# Motor_Schem_1.net
KiCad netlist of a schematic drawn in Altium Designer
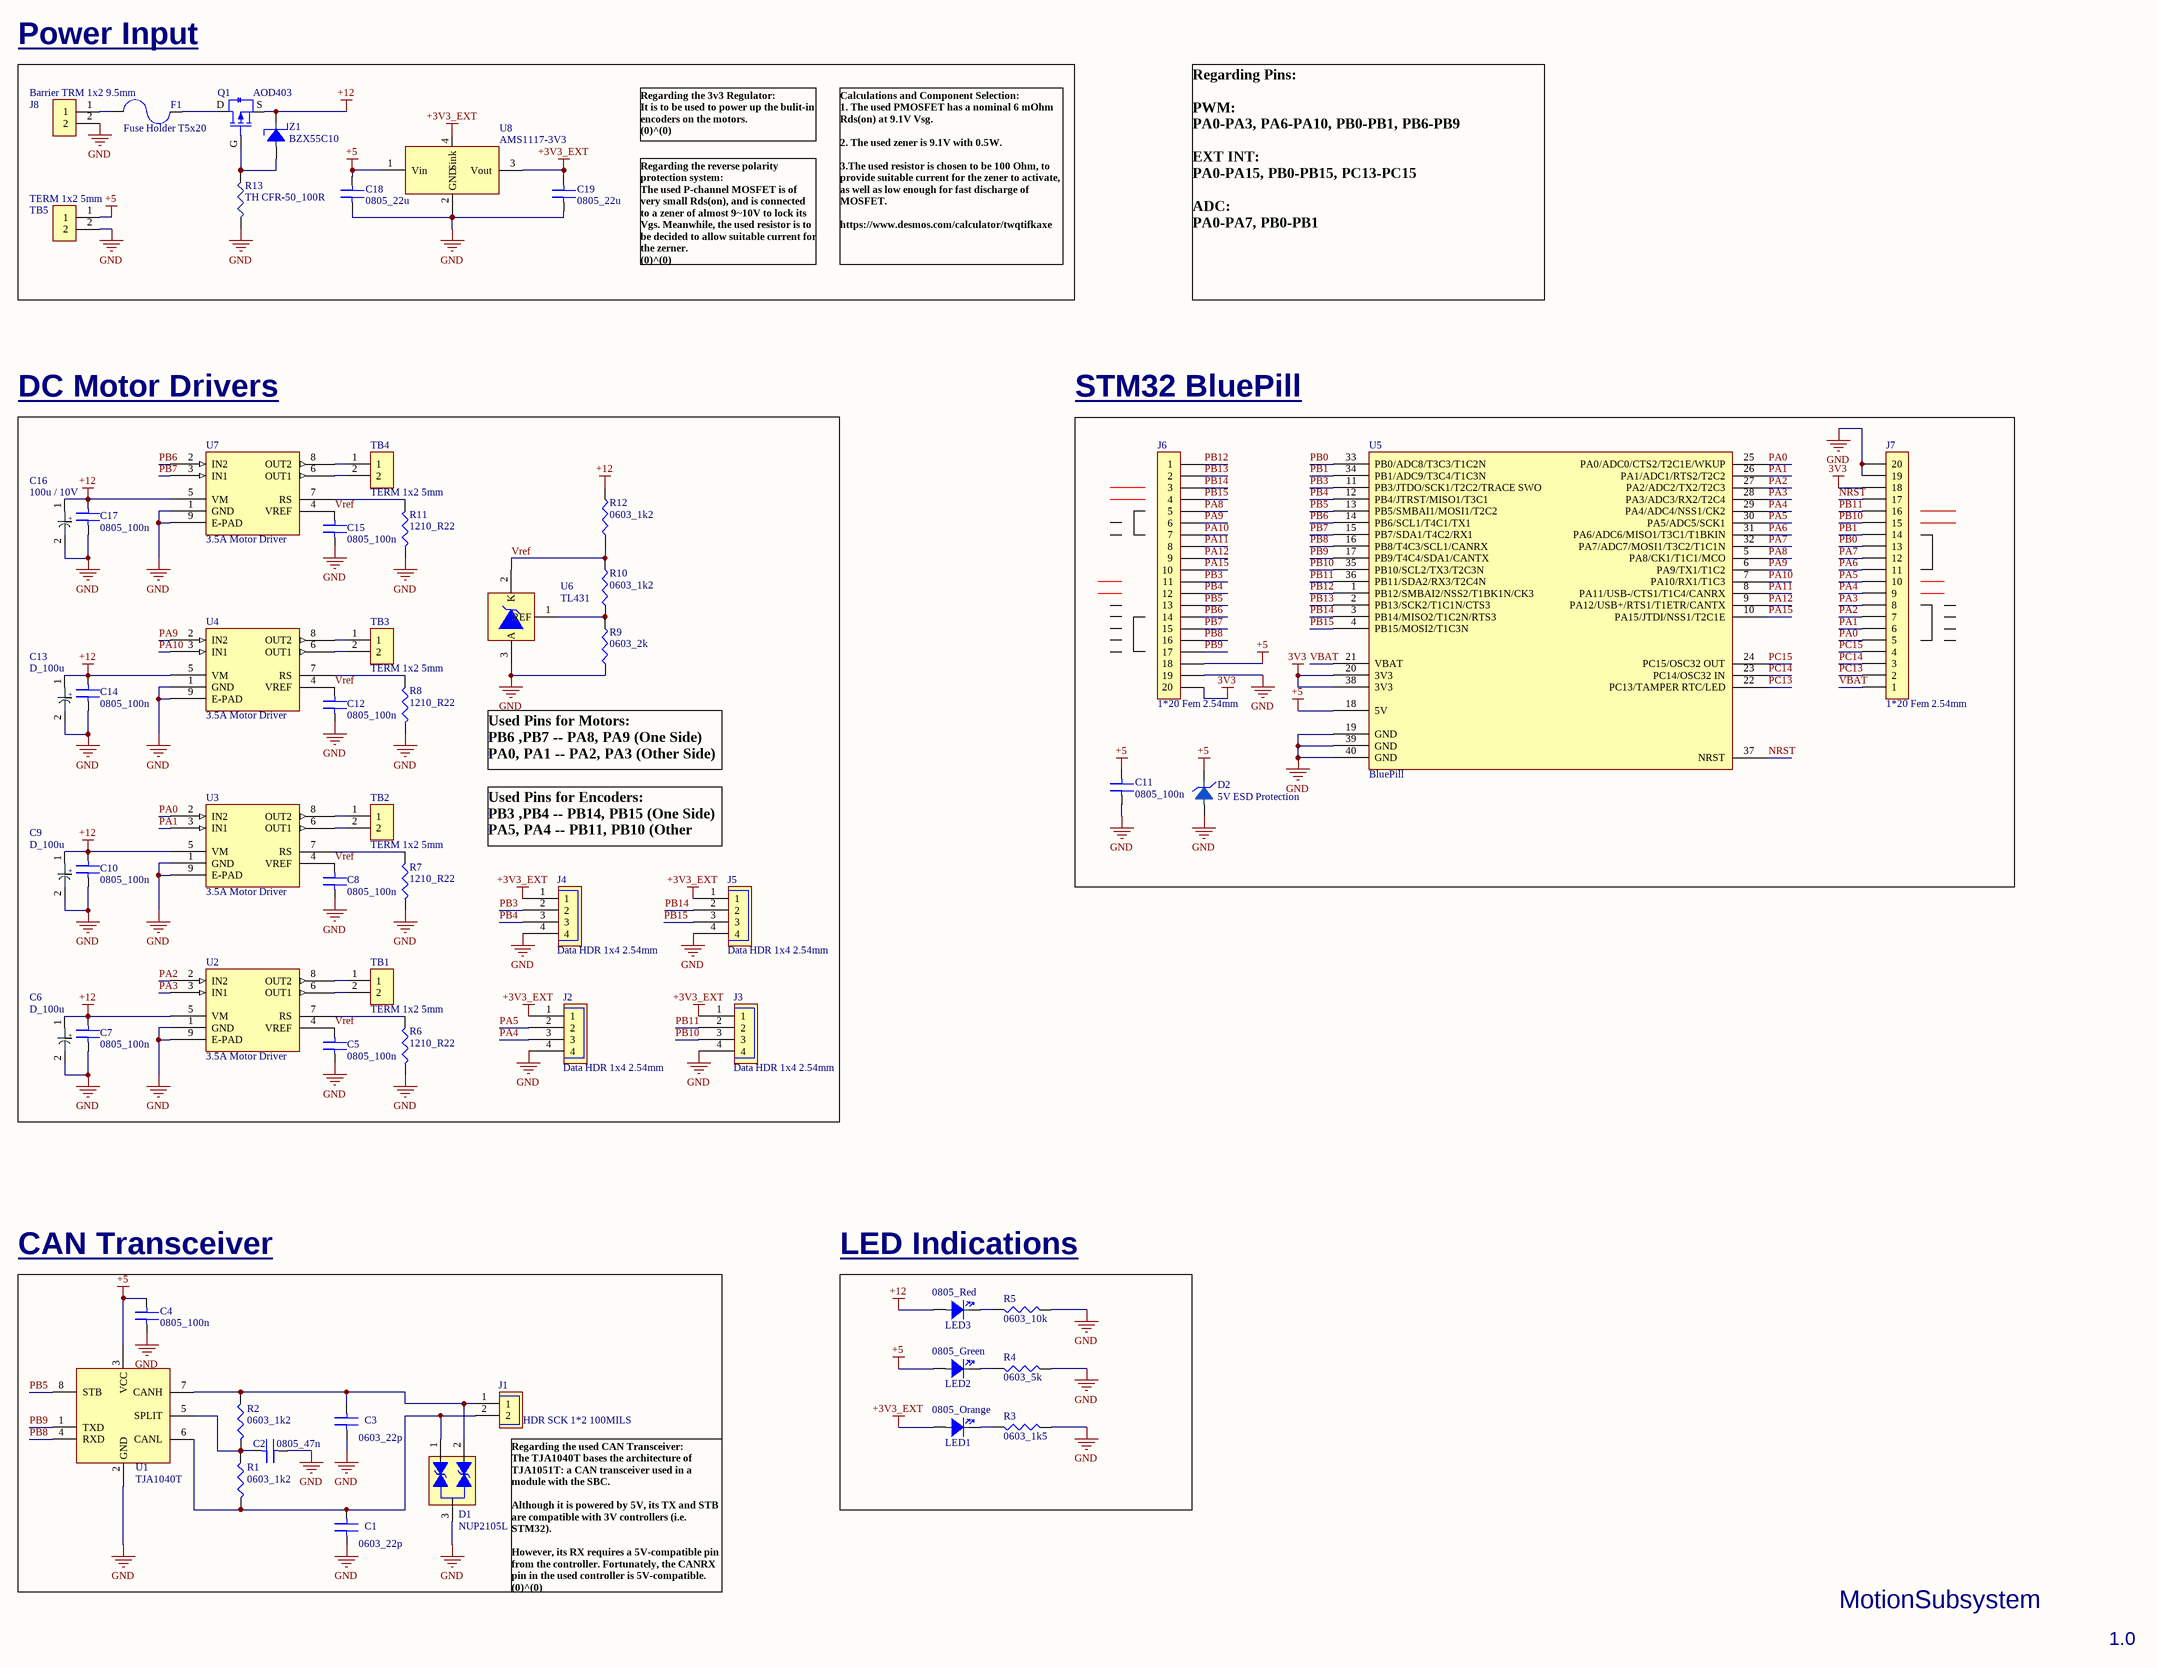
[diagram p0: Motor_Schem_1.SchDoc]

(export (version "E")
  (design (tool "Eeschema 10.0.6"))
  (components
    (comp (ref "C1")
      (value "0603_22p")
      (footprint "0603_CAP")
      (libsource (lib "TimerSMD_Components") (part "0603 Capacitor"))
    )
    (comp (ref "C2")
      (value "0805_47n")
      (footprint "C0805 - 0.1uf")
      (fields (field (name "TOLERANCE") "10%") (field (name "VOLTAGE") "25V"))
      (libsource (lib "TimerSMD_Components") (part "C2012X5R1E105K125AA"))
    )
    (comp (ref "C3")
      (value "0603_22p")
      (footprint "0603_CAP")
      (libsource (lib "TimerSMD_Components") (part "0603 Capacitor"))
    )
    (comp (ref "C4")
      (value "0805_100n")
      (footprint "C0805 - 0.1uf")
      (fields (field (name "TOLERANCE") "10%") (field (name "VOLTAGE") "25V"))
      (libsource (lib "TimerSMD_Components") (part "C2012X5R1E105K125AA"))
    )
    (comp (ref "C5")
      (value "0805_100n")
      (footprint "C0805 - 0.1uf")
      (fields (field (name "TOLERANCE") "10%") (field (name "VOLTAGE") "25V"))
      (libsource (lib "TimerSMD_Components") (part "C2012X5R1E105K125AA"))
    )
    (comp (ref "C6")
      (value "D_100u")
      (footprint "C_ALUM_D_SIZE")
      (description "Cap Aluminum 100uF 10V 20% (5 X 5.4mm) SMD 50mA 1000 hr 85°C T/R")
      (fields (field (name "TOLERANCE") "20%"))
      (libsource (lib "TimerSMD_Components") (part "EEE-1AA101WR"))
    )
    (comp (ref "C7")
      (value "0805_100n")
      (footprint "C0805 - 0.1uf")
      (fields (field (name "TOLERANCE") "10%") (field (name "VOLTAGE") "25V"))
      (libsource (lib "TimerSMD_Components") (part "C2012X5R1E105K125AA"))
    )
    (comp (ref "C8")
      (value "0805_100n")
      (footprint "C0805 - 0.1uf")
      (fields (field (name "TOLERANCE") "10%") (field (name "VOLTAGE") "25V"))
      (libsource (lib "TimerSMD_Components") (part "C2012X5R1E105K125AA"))
    )
    (comp (ref "C9")
      (value "D_100u")
      (footprint "C_ALUM_D_SIZE")
      (description "Cap Aluminum 100uF 10V 20% (5 X 5.4mm) SMD 50mA 1000 hr 85°C T/R")
      (fields (field (name "TOLERANCE") "20%"))
      (libsource (lib "TimerSMD_Components") (part "EEE-1AA101WR"))
    )
    (comp (ref "C10")
      (value "0805_100n")
      (footprint "C0805 - 0.1uf")
      (fields (field (name "TOLERANCE") "10%") (field (name "VOLTAGE") "25V"))
      (libsource (lib "TimerSMD_Components") (part "C2012X5R1E105K125AA"))
    )
    (comp (ref "C11")
      (value "0805_100n")
      (footprint "C0805 - 10uf")
      (fields (field (name "TOLERANCE") "10%"))
      (libsource (lib "TimerSMD_Components") (part "C2012X5R1C106K085AC"))
    )
    (comp (ref "C12")
      (value "0805_100n")
      (footprint "C0805 - 0.1uf")
      (fields (field (name "TOLERANCE") "10%") (field (name "VOLTAGE") "25V"))
      (libsource (lib "TimerSMD_Components") (part "C2012X5R1E105K125AA"))
    )
    (comp (ref "C13")
      (value "D_100u")
      (footprint "C_ALUM_D_SIZE")
      (description "Cap Aluminum 100uF 10V 20% (5 X 5.4mm) SMD 50mA 1000 hr 85°C T/R")
      (fields (field (name "TOLERANCE") "20%"))
      (libsource (lib "TimerSMD_Components") (part "EEE-1AA101WR"))
    )
    (comp (ref "C14")
      (value "0805_100n")
      (footprint "C0805 - 0.1uf")
      (fields (field (name "TOLERANCE") "10%") (field (name "VOLTAGE") "25V"))
      (libsource (lib "TimerSMD_Components") (part "C2012X5R1E105K125AA"))
    )
    (comp (ref "C15")
      (value "0805_100n")
      (footprint "C0805 - 0.1uf")
      (fields (field (name "TOLERANCE") "10%") (field (name "VOLTAGE") "25V"))
      (libsource (lib "TimerSMD_Components") (part "C2012X5R1E105K125AA"))
    )
    (comp (ref "C16")
      (value "100u / 10V")
      (footprint "C_ALUM_D_SIZE")
      (description "Cap Aluminum 100uF 10V 20% (5 X 5.4mm) SMD 50mA 1000 hr 85°C T/R")
      (fields (field (name "TOLERANCE") "20%"))
      (libsource (lib "TimerSMD_Components") (part "EEE-1AA101WR"))
    )
    (comp (ref "C17")
      (value "0805_100n")
      (footprint "C0805 - 0.1uf")
      (fields (field (name "TOLERANCE") "10%") (field (name "VOLTAGE") "25V"))
      (libsource (lib "TimerSMD_Components") (part "C2012X5R1E105K125AA"))
    )
    (comp (ref "C18")
      (value "0805_22u")
      (footprint "C0805 - 0.1uf")
      (fields (field (name "TOLERANCE") "10%") (field (name "VOLTAGE") "25V"))
      (libsource (lib "TimerSMD_Components") (part "C2012X5R1E105K125AA"))
    )
    (comp (ref "C19")
      (value "0805_22u")
      (footprint "C0805 - 0.1uf")
      (fields (field (name "TOLERANCE") "10%") (field (name "VOLTAGE") "25V"))
      (libsource (lib "TimerSMD_Components") (part "C2012X5R1E105K125AA"))
    )
    (comp (ref "D1")
      (value "NUP2105L")
      (footprint "SO-23")
      (description "ESD Protection Dual Diode for CAN Bus Line Protection")
      (libsource (lib "TimerSMD_Components") (part "NUP2105L"))
    )
    (comp (ref "D2")
      (value "5V ESD Protection")
      (footprint "D0-214AA")
      (libsource (lib "TimerSMD_Components") (part "SMBJ5.0A"))
    )
    (comp (ref "F1")
      (value "Fuse Holder T5x20")
      (footprint "FUSE")
      (libsource (lib "CAD_Symbols") (part "FUSE_T5x20"))
    )
    (comp (ref "J1")
      (value "HDR SCK 1*2 100MILS")
      (footprint "DHDR 1*2 2,54MM")
      (description "Conn Shrouded Header HDR 2 POS 2.54mm Solder ST Thru-Hole")
      (libsource (lib "CAD_Symbols") (part "2-Pin Data Connector"))
    )
    (comp (ref "J2")
      (value "Data HDR 1x4 2.54mm")
      (footprint "DHDR_1x4_2.54mm")
      (description "MTA-100 Series, 2.54mm Pitch 4 Way 1 RowStraight PCB Header, Solder Term, 5A")
      (libsource (lib "CAD_Symbols") (part "4-Pin Data Connector"))
    )
    (comp (ref "J3")
      (value "Data HDR 1x4 2.54mm")
      (footprint "DHDR_1x4_2.54mm")
      (description "MTA-100 Series, 2.54mm Pitch 4 Way 1 RowStraight PCB Header, Solder Term, 5A")
      (libsource (lib "CAD_Symbols") (part "4-Pin Data Connector"))
    )
    (comp (ref "J4")
      (value "Data HDR 1x4 2.54mm")
      (footprint "DHDR_1x4_2.54mm")
      (description "MTA-100 Series, 2.54mm Pitch 4 Way 1 RowStraight PCB Header, Solder Term, 5A")
      (libsource (lib "CAD_Symbols") (part "4-Pin Data Connector"))
    )
    (comp (ref "J5")
      (value "Data HDR 1x4 2.54mm")
      (footprint "DHDR_1x4_2.54mm")
      (description "MTA-100 Series, 2.54mm Pitch 4 Way 1 RowStraight PCB Header, Solder Term, 5A")
      (libsource (lib "CAD_Symbols") (part "4-Pin Data Connector"))
    )
    (comp (ref "J6")
      (value "1*20 Fem 2.54mm")
      (footprint "20*1 FEM 2.54mm")
      (libsource (lib "CAD_Symbols") (part "1*20 Fem 2.54mm"))
    )
    (comp (ref "J7")
      (value "1*20 Fem 2.54mm")
      (footprint "20*1 FEM 2.54mm")
      (libsource (lib "") (part "1*20 Fem 2.54mm_1"))
    )
    (comp (ref "J8")
      (value "Barrier TRM 1x2 9.5mm")
      (footprint "BARRIER_9.5MM")
      (description "CONN BARRIER STRIP 2CIRC 0.374\"")
      (libsource (lib "CAD_Symbols") (part "Barrier BLK"))
    )
    (comp (ref "LED1")
      (value "0805_Orange")
      (footprint "0805_LED")
      (libsource (lib "TimerSMD_Components") (part "0805LED"))
    )
    (comp (ref "LED2")
      (value "0805_Green")
      (footprint "0805_LED")
      (libsource (lib "TimerSMD_Components") (part "0805LED"))
    )
    (comp (ref "LED3")
      (value "0805_Red")
      (footprint "0805_LED")
      (libsource (lib "TimerSMD_Components") (part "0805LED"))
    )
    (comp (ref "Q1")
      (value "AOD403")
      (footprint "DPAK")
      (description "MOSFET Transistor P-Channel 30V 15A 3.5V @ 250uA 6mΩ @ 20A,20V 2.5W TO-252-2(DPAK)")
      (libsource (lib "TimerSMD_Components") (part "AOD403"))
    )
    (comp (ref "R1")
      (value "0603_1k2")
      (footprint "0603_CAP")
      (libsource (lib "TimerSMD_Components") (part "0603 Resistor"))
    )
    (comp (ref "R2")
      (value "0603_1k2")
      (footprint "0603_CAP")
      (libsource (lib "TimerSMD_Components") (part "0603 Resistor"))
    )
    (comp (ref "R3")
      (value "0603_1k5")
      (footprint "0603_CAP")
      (libsource (lib "TimerSMD_Components") (part "0603 Resistor"))
    )
    (comp (ref "R4")
      (value "0603_5k")
      (footprint "0603_CAP")
      (libsource (lib "TimerSMD_Components") (part "0603 Resistor"))
    )
    (comp (ref "R5")
      (value "0603_10k")
      (footprint "0603_CAP")
      (libsource (lib "TimerSMD_Components") (part "0603 Resistor"))
    )
    (comp (ref "R6")
      (value "1210_R22")
      (footprint "1210_R")
      (libsource (lib "TimerSMD_Components") (part "1210 Resistor"))
    )
    (comp (ref "R7")
      (value "1210_R22")
      (footprint "1210_R")
      (libsource (lib "TimerSMD_Components") (part "1210 Resistor"))
    )
    (comp (ref "R8")
      (value "1210_R22")
      (footprint "1210_R")
      (libsource (lib "TimerSMD_Components") (part "1210 Resistor"))
    )
    (comp (ref "R9")
      (value "0603_2k")
      (footprint "0603_CAP")
      (libsource (lib "TimerSMD_Components") (part "0603 Resistor"))
    )
    (comp (ref "R10")
      (value "0603_1k2")
      (footprint "0603_CAP")
      (libsource (lib "TimerSMD_Components") (part "0603 Resistor"))
    )
    (comp (ref "R11")
      (value "1210_R22")
      (footprint "1210_R")
      (libsource (lib "TimerSMD_Components") (part "1210 Resistor"))
    )
    (comp (ref "R12")
      (value "0603_1k2")
      (footprint "0603_CAP")
      (libsource (lib "TimerSMD_Components") (part "0603 Resistor"))
    )
    (comp (ref "R13")
      (value "TH CFR-50_100R")
      (footprint "R_THT_CFR-50")
      (description "General Type Carbon Film Resistor 330Ohm 1/2W 5% Axial Bulk")
      (fields (field (name "TOLERANCE") "5%"))
      (libsource (lib "CAD_Symbols") (part "TH CFR-50 Resis"))
    )
    (comp (ref "TB1")
      (value "TERM 1x2 5mm")
      (footprint "Terminal_5mm")
      (fields (field (name "VOLTAGE") "300V"))
      (libsource (lib "CAD_Symbols") (part "Terminal BLK Green"))
    )
    (comp (ref "TB2")
      (value "TERM 1x2 5mm")
      (footprint "Terminal_5mm")
      (fields (field (name "VOLTAGE") "300V"))
      (libsource (lib "CAD_Symbols") (part "Terminal BLK Green"))
    )
    (comp (ref "TB3")
      (value "TERM 1x2 5mm")
      (footprint "Terminal_5mm")
      (fields (field (name "VOLTAGE") "300V"))
      (libsource (lib "CAD_Symbols") (part "Terminal BLK Green"))
    )
    (comp (ref "TB4")
      (value "TERM 1x2 5mm")
      (footprint "Terminal_5mm")
      (fields (field (name "VOLTAGE") "300V"))
      (libsource (lib "CAD_Symbols") (part "Terminal BLK Green"))
    )
    (comp (ref "TB5")
      (value "TERM 1x2 5mm")
      (footprint "Terminal_5mm")
      (fields (field (name "VOLTAGE") "300V"))
      (libsource (lib "") (part "Terminal BLK Green_1"))
    )
    (comp (ref "U1")
      (value "TJA1040T")
      (footprint "SOP8 - duplicate")
      (description "CAN Transceiver")
      (libsource (lib "TimerSMD_Components") (part "TJA1040T"))
    )
    (comp (ref "U2")
      (value "3.5A Motor Driver")
      (footprint "HSOP8")
      (libsource (lib "TimerSMD_Components") (part "TB67H450FNG"))
    )
    (comp (ref "U3")
      (value "3.5A Motor Driver")
      (footprint "HSOP8")
      (libsource (lib "TimerSMD_Components") (part "TB67H450FNG"))
    )
    (comp (ref "U4")
      (value "3.5A Motor Driver")
      (footprint "HSOP8")
      (libsource (lib "TimerSMD_Components") (part "TB67H450FNG"))
    )
    (comp (ref "U5")
      (value "BluePill")
      (footprint "BluePill")
      (libsource (lib "CAD_Symbols") (part "STM32 BluePill"))
    )
    (comp (ref "U6")
      (value "TL431")
      (footprint "SO-23")
      (description "SMD Voltage References SOT-23")
      (libsource (lib "TimerSMD_Components") (part "TL431"))
    )
    (comp (ref "U7")
      (value "3.5A Motor Driver")
      (footprint "HSOP8")
      (libsource (lib "TimerSMD_Components") (part "TB67H450FNG"))
    )
    (comp (ref "U8")
      (value "AMS1117-3V3")
      (footprint "SOT-223")
      (libsource (lib "TimerSMD_Components") (part "AMS1117 - 3V3"))
    )
    (comp (ref "Z1")
      (value "BZX55C10")
      (footprint "DO-35")
      (description "TH Zener Diode DO-35")
      (libsource (lib "CAD_Symbols") (part "Zener_DO-35"))
    )
  )
  (nets
    (net (code "1") (name "+3V3_EXT") (class "Default")
      (node (ref "C19") (pin "2") (pinfunction "2_2") (pintype "passive"))
      (node (ref "J2") (pin "1") (pinfunction "1_1") (pintype "passive"))
      (node (ref "J3") (pin "1") (pinfunction "1_1") (pintype "passive"))
      (node (ref "J4") (pin "1") (pinfunction "1_1") (pintype "passive"))
      (node (ref "J5") (pin "1") (pinfunction "1_1") (pintype "passive"))
      (node (ref "LED1") (pin "1") (pinfunction "Anode_1") (pintype "passive"))
      (node (ref "U8") (pin "3") (pinfunction "Vout_3") (pintype "passive"))
      (node (ref "U8") (pin "4") (pinfunction "Sink_4") (pintype "passive"))
    )
    (net (code "2") (name "+5") (class "Default")
      (node (ref "C11") (pin "2") (pinfunction "2_2") (pintype "passive"))
      (node (ref "C18") (pin "2") (pinfunction "2_2") (pintype "passive"))
      (node (ref "C4") (pin "2") (pinfunction "2_2") (pintype "passive"))
      (node (ref "D2") (pin "K") (pinfunction "Cathode_K") (pintype "passive"))
      (node (ref "J6") (pin "18") (pinfunction "18_18") (pintype "passive"))
      (node (ref "LED2") (pin "1") (pinfunction "Anode_1") (pintype "passive"))
      (node (ref "TB5") (pin "1") (pinfunction "1_1") (pintype "passive"))
      (node (ref "U1") (pin "3") (pinfunction "VCC_3") (pintype "passive"))
      (node (ref "U5") (pin "18") (pinfunction "5V_18") (pintype "passive"))
      (node (ref "U8") (pin "1") (pinfunction "Vin_1") (pintype "passive"))
    )
    (net (code "3") (name "+12") (class "Default")
      (node (ref "C10") (pin "2") (pinfunction "2_2") (pintype "passive"))
      (node (ref "C13") (pin "1") (pinfunction "1_1") (pintype "passive"))
      (node (ref "C14") (pin "2") (pinfunction "2_2") (pintype "passive"))
      (node (ref "C16") (pin "1") (pinfunction "1_1") (pintype "passive"))
      (node (ref "C17") (pin "2") (pinfunction "2_2") (pintype "passive"))
      (node (ref "C6") (pin "1") (pinfunction "1_1") (pintype "passive"))
      (node (ref "C7") (pin "2") (pinfunction "2_2") (pintype "passive"))
      (node (ref "C9") (pin "1") (pinfunction "1_1") (pintype "passive"))
      (node (ref "LED3") (pin "1") (pinfunction "Anode_1") (pintype "passive"))
      (node (ref "Q1") (pin "S") (pinfunction "S_S") (pintype "passive"))
      (node (ref "R12") (pin "1") (pinfunction "1_1") (pintype "passive"))
      (node (ref "U2") (pin "5") (pinfunction "VM_5") (pintype "power_in"))
      (node (ref "U3") (pin "5") (pinfunction "VM_5") (pintype "power_in"))
      (node (ref "U4") (pin "5") (pinfunction "VM_5") (pintype "power_in"))
      (node (ref "U7") (pin "5") (pinfunction "VM_5") (pintype "power_in"))
      (node (ref "Z1") (pin "K") (pinfunction "Cathode_K") (pintype "passive"))
    )
    (net (code "4") (name "/NRST") (class "Default")
      (node (ref "J7") (pin "17") (pinfunction "17_17") (pintype "passive"))
      (node (ref "U5") (pin "37") (pinfunction "NRST_37") (pintype "passive"))
    )
    (net (code "5") (name "/PA0") (class "Default")
      (node (ref "J7") (pin "5") (pinfunction "5_5") (pintype "passive"))
      (node (ref "U3") (pin "2") (pinfunction "IN2_2") (pintype "input"))
      (node (ref "U5") (pin "25") (pinfunction "PA0/ADC0/CTS2/T2C1E/WKUP_25") (pintype "passive"))
    )
    (net (code "6") (name "/PA1") (class "Default")
      (node (ref "J7") (pin "6") (pinfunction "6_6") (pintype "passive"))
      (node (ref "U3") (pin "3") (pinfunction "IN1_3") (pintype "input"))
      (node (ref "U5") (pin "26") (pinfunction "PA1/ADC1/RTS2/T2C2_26") (pintype "passive"))
    )
    (net (code "7") (name "/PA2") (class "Default")
      (node (ref "J7") (pin "7") (pinfunction "7_7") (pintype "passive"))
      (node (ref "U2") (pin "2") (pinfunction "IN2_2") (pintype "input"))
      (node (ref "U5") (pin "27") (pinfunction "PA2/ADC2/TX2/T2C3_27") (pintype "passive"))
    )
    (net (code "8") (name "/PA3") (class "Default")
      (node (ref "J7") (pin "8") (pinfunction "8_8") (pintype "passive"))
      (node (ref "U2") (pin "3") (pinfunction "IN1_3") (pintype "input"))
      (node (ref "U5") (pin "28") (pinfunction "PA3/ADC3/RX2/T2C4_28") (pintype "passive"))
    )
    (net (code "9") (name "/PA4") (class "Default")
      (node (ref "J2") (pin "3") (pinfunction "3_3") (pintype "passive"))
      (node (ref "J7") (pin "9") (pinfunction "9_9") (pintype "passive"))
      (node (ref "U5") (pin "29") (pinfunction "PA4/ADC4/NSS1/CK2_29") (pintype "passive"))
    )
    (net (code "10") (name "/PA5") (class "Default")
      (node (ref "J2") (pin "2") (pinfunction "2_2") (pintype "passive"))
      (node (ref "J7") (pin "10") (pinfunction "10_10") (pintype "passive"))
      (node (ref "U5") (pin "30") (pinfunction "PA5/ADC5/SCK1_30") (pintype "passive"))
    )
    (net (code "11") (name "/PA6") (class "Default")
      (node (ref "J7") (pin "11") (pinfunction "11_11") (pintype "passive"))
      (node (ref "U5") (pin "31") (pinfunction "PA6/ADC6/MISO1/T3C1/T1BKIN_31") (pintype "passive"))
    )
    (net (code "12") (name "/PA7") (class "Default")
      (node (ref "J7") (pin "12") (pinfunction "12_12") (pintype "passive"))
      (node (ref "U5") (pin "32") (pinfunction "PA7/ADC7/MOSI1/T3C2/T1C1N_32") (pintype "passive"))
    )
    (net (code "13") (name "/PA8") (class "Default")
      (node (ref "J6") (pin "5") (pinfunction "5_5") (pintype "passive"))
      (node (ref "U5") (pin "5") (pinfunction "PA8/CK1/T1C1/MCO_5") (pintype "passive"))
    )
    (net (code "14") (name "/PA9") (class "Default")
      (node (ref "J6") (pin "6") (pinfunction "6_6") (pintype "passive"))
      (node (ref "U4") (pin "2") (pinfunction "IN2_2") (pintype "input"))
      (node (ref "U5") (pin "6") (pinfunction "PA9/TX1/T1C2_6") (pintype "passive"))
    )
    (net (code "15") (name "/PA10") (class "Default")
      (node (ref "J6") (pin "7") (pinfunction "7_7") (pintype "passive"))
      (node (ref "U4") (pin "3") (pinfunction "IN1_3") (pintype "input"))
      (node (ref "U5") (pin "7") (pinfunction "PA10/RX1/T1C3_7") (pintype "passive"))
    )
    (net (code "16") (name "/PA11") (class "Default")
      (node (ref "J6") (pin "8") (pinfunction "8_8") (pintype "passive"))
      (node (ref "U5") (pin "8") (pinfunction "PA11/USB-/CTS1/T1C4/CANRX_8") (pintype "passive"))
    )
    (net (code "17") (name "/PA12") (class "Default")
      (node (ref "J6") (pin "9") (pinfunction "9_9") (pintype "passive"))
      (node (ref "U5") (pin "9") (pinfunction "PA12/USB+/RTS1/T1ETR/CANTX_9") (pintype "passive"))
    )
    (net (code "18") (name "/PA15") (class "Default")
      (node (ref "J6") (pin "10") (pinfunction "10_10") (pintype "passive"))
      (node (ref "U5") (pin "10") (pinfunction "PA15/JTDI/NSS1/T2C1E_10") (pintype "passive"))
    )
    (net (code "19") (name "/PB0") (class "Default")
      (node (ref "J7") (pin "13") (pinfunction "13_13") (pintype "passive"))
      (node (ref "U5") (pin "33") (pinfunction "PB0/ADC8/T3C3/T1C2N_33") (pintype "passive"))
    )
    (net (code "20") (name "/PB1") (class "Default")
      (node (ref "J7") (pin "14") (pinfunction "14_14") (pintype "passive"))
      (node (ref "U5") (pin "34") (pinfunction "PB1/ADC9/T3C4/T1C3N_34") (pintype "passive"))
    )
    (net (code "21") (name "/PB3") (class "Default")
      (node (ref "J4") (pin "2") (pinfunction "2_2") (pintype "passive"))
      (node (ref "J6") (pin "11") (pinfunction "11_11") (pintype "passive"))
      (node (ref "U5") (pin "11") (pinfunction "PB3/JTDO/SCK1/T2C2/TRACE_SWO_11") (pintype "passive"))
    )
    (net (code "22") (name "/PB4") (class "Default")
      (node (ref "J4") (pin "3") (pinfunction "3_3") (pintype "passive"))
      (node (ref "J6") (pin "12") (pinfunction "12_12") (pintype "passive"))
      (node (ref "U5") (pin "12") (pinfunction "PB4/JTRST/MISO1/T3C1_12") (pintype "passive"))
    )
    (net (code "23") (name "/PB5") (class "Default")
      (node (ref "J6") (pin "13") (pinfunction "13_13") (pintype "passive"))
      (node (ref "U1") (pin "8") (pinfunction "STB_8") (pintype "passive"))
      (node (ref "U5") (pin "13") (pinfunction "PB5/SMBAI1/MOSI1/T2C2_13") (pintype "passive"))
    )
    (net (code "24") (name "/PB6") (class "Default")
      (node (ref "J6") (pin "14") (pinfunction "14_14") (pintype "passive"))
      (node (ref "U5") (pin "14") (pinfunction "PB6/SCL1/T4C1/TX1_14") (pintype "passive"))
      (node (ref "U7") (pin "2") (pinfunction "IN2_2") (pintype "input"))
    )
    (net (code "25") (name "/PB7") (class "Default")
      (node (ref "J6") (pin "15") (pinfunction "15_15") (pintype "passive"))
      (node (ref "U5") (pin "15") (pinfunction "PB7/SDA1/T4C2/RX1_15") (pintype "passive"))
      (node (ref "U7") (pin "3") (pinfunction "IN1_3") (pintype "input"))
    )
    (net (code "26") (name "/PB8") (class "Default")
      (node (ref "J6") (pin "16") (pinfunction "16_16") (pintype "passive"))
      (node (ref "U1") (pin "4") (pinfunction "RXD_4") (pintype "passive"))
      (node (ref "U5") (pin "16") (pinfunction "PB8/T4C3/SCL1/CANRX_16") (pintype "passive"))
    )
    (net (code "27") (name "/PB9") (class "Default")
      (node (ref "J6") (pin "17") (pinfunction "17_17") (pintype "passive"))
      (node (ref "U1") (pin "1") (pinfunction "TXD_1") (pintype "passive"))
      (node (ref "U5") (pin "17") (pinfunction "PB9/T4C4/SDA1/CANTX_17") (pintype "passive"))
    )
    (net (code "28") (name "/PB10") (class "Default")
      (node (ref "J3") (pin "3") (pinfunction "3_3") (pintype "passive"))
      (node (ref "J7") (pin "15") (pinfunction "15_15") (pintype "passive"))
      (node (ref "U5") (pin "35") (pinfunction "PB10/SCL2/TX3/T2C3N_35") (pintype "passive"))
    )
    (net (code "29") (name "/PB11") (class "Default")
      (node (ref "J3") (pin "2") (pinfunction "2_2") (pintype "passive"))
      (node (ref "J7") (pin "16") (pinfunction "16_16") (pintype "passive"))
      (node (ref "U5") (pin "36") (pinfunction "PB11/SDA2/RX3/T2C4N_36") (pintype "passive"))
    )
    (net (code "30") (name "/PB12") (class "Default")
      (node (ref "J6") (pin "1") (pinfunction "1_1") (pintype "passive"))
      (node (ref "U5") (pin "1") (pinfunction "PB12/SMBAI2/NSS2/T1BK1N/CK3_1") (pintype "passive"))
    )
    (net (code "31") (name "/PB13") (class "Default")
      (node (ref "J6") (pin "2") (pinfunction "2_2") (pintype "passive"))
      (node (ref "U5") (pin "2") (pinfunction "PB13/SCK2/T1C1N/CTS3_2") (pintype "passive"))
    )
    (net (code "32") (name "/PB14") (class "Default")
      (node (ref "J5") (pin "2") (pinfunction "2_2") (pintype "passive"))
      (node (ref "J6") (pin "3") (pinfunction "3_3") (pintype "passive"))
      (node (ref "U5") (pin "3") (pinfunction "PB14/MISO2/T1C2N/RTS3_3") (pintype "passive"))
    )
    (net (code "33") (name "/PB15") (class "Default")
      (node (ref "J5") (pin "3") (pinfunction "3_3") (pintype "passive"))
      (node (ref "J6") (pin "4") (pinfunction "4_4") (pintype "passive"))
      (node (ref "U5") (pin "4") (pinfunction "PB15/MOSI2/T1C3N_4") (pintype "passive"))
    )
    (net (code "34") (name "/PC13") (class "Default")
      (node (ref "J7") (pin "2") (pinfunction "2_2") (pintype "passive"))
      (node (ref "U5") (pin "22") (pinfunction "PC13/TAMPER_RTC/LED_22") (pintype "passive"))
    )
    (net (code "35") (name "/PC14") (class "Default")
      (node (ref "J7") (pin "3") (pinfunction "3_3") (pintype "passive"))
      (node (ref "U5") (pin "23") (pinfunction "PC14/OSC32_IN_23") (pintype "passive"))
    )
    (net (code "36") (name "/PC15") (class "Default")
      (node (ref "J7") (pin "4") (pinfunction "4_4") (pintype "passive"))
      (node (ref "U5") (pin "24") (pinfunction "PC15/OSC32_OUT_24") (pintype "passive"))
    )
    (net (code "37") (name "/VBAT") (class "Default")
      (node (ref "J7") (pin "1") (pinfunction "1_1") (pintype "passive"))
      (node (ref "U5") (pin "21") (pinfunction "VBAT_21") (pintype "passive"))
    )
    (net (code "38") (name "/Vref") (class "Default")
      (node (ref "C12") (pin "2") (pinfunction "2_2") (pintype "passive"))
      (node (ref "C15") (pin "2") (pinfunction "2_2") (pintype "passive"))
      (node (ref "C5") (pin "2") (pinfunction "2_2") (pintype "passive"))
      (node (ref "C8") (pin "2") (pinfunction "2_2") (pintype "passive"))
      (node (ref "R10") (pin "2") (pinfunction "2_2") (pintype "passive"))
      (node (ref "R12") (pin "2") (pinfunction "2_2") (pintype "passive"))
      (node (ref "U2") (pin "4") (pinfunction "VREF_4") (pintype "passive"))
      (node (ref "U3") (pin "4") (pinfunction "VREF_4") (pintype "passive"))
      (node (ref "U4") (pin "4") (pinfunction "VREF_4") (pintype "passive"))
      (node (ref "U6") (pin "2") (pinfunction "K_2") (pintype "passive"))
      (node (ref "U7") (pin "4") (pinfunction "VREF_4") (pintype "passive"))
    )
    (net (code "39") (name "3V3") (class "Default")
      (node (ref "J6") (pin "20") (pinfunction "20_20") (pintype "passive"))
      (node (ref "J7") (pin "18") (pinfunction "18_18") (pintype "passive"))
      (node (ref "U5") (pin "20") (pinfunction "3V3_20") (pintype "passive"))
      (node (ref "U5") (pin "38") (pinfunction "3V3_38") (pintype "passive"))
    )
    (net (code "40") (name "GND") (class "Default")
      (node (ref "C1") (pin "1") (pinfunction "1_1") (pintype "passive"))
      (node (ref "C10") (pin "1") (pinfunction "1_1") (pintype "passive"))
      (node (ref "C11") (pin "1") (pinfunction "1_1") (pintype "passive"))
      (node (ref "C12") (pin "1") (pinfunction "1_1") (pintype "passive"))
      (node (ref "C13") (pin "2") (pinfunction "2_2") (pintype "passive"))
      (node (ref "C14") (pin "1") (pinfunction "1_1") (pintype "passive"))
      (node (ref "C15") (pin "1") (pinfunction "1_1") (pintype "passive"))
      (node (ref "C16") (pin "2") (pinfunction "2_2") (pintype "passive"))
      (node (ref "C17") (pin "1") (pinfunction "1_1") (pintype "passive"))
      (node (ref "C18") (pin "1") (pinfunction "1_1") (pintype "passive"))
      (node (ref "C19") (pin "1") (pinfunction "1_1") (pintype "passive"))
      (node (ref "C2") (pin "1") (pinfunction "1_1") (pintype "passive"))
      (node (ref "C3") (pin "1") (pinfunction "1_1") (pintype "passive"))
      (node (ref "C4") (pin "1") (pinfunction "1_1") (pintype "passive"))
      (node (ref "C5") (pin "1") (pinfunction "1_1") (pintype "passive"))
      (node (ref "C6") (pin "2") (pinfunction "2_2") (pintype "passive"))
      (node (ref "C7") (pin "1") (pinfunction "1_1") (pintype "passive"))
      (node (ref "C8") (pin "1") (pinfunction "1_1") (pintype "passive"))
      (node (ref "C9") (pin "2") (pinfunction "2_2") (pintype "passive"))
      (node (ref "D1") (pin "3") (pinfunction "IN3_3") (pintype "passive"))
      (node (ref "D2") (pin "A") (pinfunction "Anode_A") (pintype "passive"))
      (node (ref "J2") (pin "4") (pinfunction "4_4") (pintype "passive"))
      (node (ref "J3") (pin "4") (pinfunction "4_4") (pintype "passive"))
      (node (ref "J4") (pin "4") (pinfunction "4_4") (pintype "passive"))
      (node (ref "J5") (pin "4") (pinfunction "4_4") (pintype "passive"))
      (node (ref "J6") (pin "19") (pinfunction "19_19") (pintype "passive"))
      (node (ref "J7") (pin "19") (pinfunction "19_19") (pintype "passive"))
      (node (ref "J7") (pin "20") (pinfunction "20_20") (pintype "passive"))
      (node (ref "J8") (pin "2") (pinfunction "2_2") (pintype "passive"))
      (node (ref "R11") (pin "1") (pinfunction "1_1") (pintype "passive"))
      (node (ref "R13") (pin "1") (pinfunction "1_1") (pintype "passive"))
      (node (ref "R3") (pin "1") (pinfunction "1_1") (pintype "passive"))
      (node (ref "R4") (pin "1") (pinfunction "1_1") (pintype "passive"))
      (node (ref "R5") (pin "1") (pinfunction "1_1") (pintype "passive"))
      (node (ref "R6") (pin "1") (pinfunction "1_1") (pintype "passive"))
      (node (ref "R7") (pin "1") (pinfunction "1_1") (pintype "passive"))
      (node (ref "R8") (pin "1") (pinfunction "1_1") (pintype "passive"))
      (node (ref "R9") (pin "1") (pinfunction "1_1") (pintype "passive"))
      (node (ref "TB5") (pin "2") (pinfunction "2_2") (pintype "passive"))
      (node (ref "U1") (pin "2") (pinfunction "GND_2") (pintype "passive"))
      (node (ref "U2") (pin "1") (pinfunction "GND_1") (pintype "power_in"))
      (node (ref "U2") (pin "9") (pinfunction "E-PAD_9") (pintype "power_in"))
      (node (ref "U3") (pin "1") (pinfunction "GND_1") (pintype "power_in"))
      (node (ref "U3") (pin "9") (pinfunction "E-PAD_9") (pintype "power_in"))
      (node (ref "U4") (pin "1") (pinfunction "GND_1") (pintype "power_in"))
      (node (ref "U4") (pin "9") (pinfunction "E-PAD_9") (pintype "power_in"))
      (node (ref "U5") (pin "19") (pinfunction "GND_19") (pintype "passive"))
      (node (ref "U5") (pin "39") (pinfunction "GND_39") (pintype "passive"))
      (node (ref "U5") (pin "40") (pinfunction "GND_40") (pintype "passive"))
      (node (ref "U6") (pin "3") (pinfunction "A_3") (pintype "passive"))
      (node (ref "U7") (pin "1") (pinfunction "GND_1") (pintype "power_in"))
      (node (ref "U7") (pin "9") (pinfunction "E-PAD_9") (pintype "power_in"))
      (node (ref "U8") (pin "2") (pinfunction "GND_2") (pintype "passive"))
    )
    (net (code "41") (name "Net-(D1-IN1)") (class "Default")
      (node (ref "C1") (pin "2") (pinfunction "2_2") (pintype "passive"))
      (node (ref "D1") (pin "1") (pinfunction "IN1_1") (pintype "passive"))
      (node (ref "J1") (pin "2") (pinfunction "2_2") (pintype "passive"))
      (node (ref "R1") (pin "1") (pinfunction "1_1") (pintype "passive"))
      (node (ref "U1") (pin "6") (pinfunction "CANL_6") (pintype "passive"))
    )
    (net (code "42") (name "Net-(D1-IN2)") (class "Default")
      (node (ref "C3") (pin "2") (pinfunction "2_2") (pintype "passive"))
      (node (ref "D1") (pin "2") (pinfunction "IN2_2") (pintype "passive"))
      (node (ref "J1") (pin "1") (pinfunction "1_1") (pintype "passive"))
      (node (ref "R2") (pin "2") (pinfunction "2_2") (pintype "passive"))
      (node (ref "U1") (pin "7") (pinfunction "CANH_7") (pintype "passive"))
    )
    (net (code "43") (name "Net-(F1-Pad1)") (class "Default")
      (node (ref "F1") (pin "1") (pinfunction "1_1") (pintype "passive"))
      (node (ref "J8") (pin "1") (pinfunction "1_1") (pintype "passive"))
    )
    (net (code "44") (name "Net-(F1-Pad2)") (class "Default")
      (node (ref "F1") (pin "2") (pinfunction "2_2") (pintype "passive"))
      (node (ref "Q1") (pin "D") (pinfunction "D_D") (pintype "passive"))
    )
    (net (code "45") (name "Net-(LED1-Cathode)") (class "Default")
      (node (ref "LED1") (pin "2") (pinfunction "Cathode_2") (pintype "passive"))
      (node (ref "R3") (pin "2") (pinfunction "2_2") (pintype "passive"))
    )
    (net (code "46") (name "Net-(LED2-Cathode)") (class "Default")
      (node (ref "LED2") (pin "2") (pinfunction "Cathode_2") (pintype "passive"))
      (node (ref "R4") (pin "2") (pinfunction "2_2") (pintype "passive"))
    )
    (net (code "47") (name "Net-(LED3-Cathode)") (class "Default")
      (node (ref "LED3") (pin "2") (pinfunction "Cathode_2") (pintype "passive"))
      (node (ref "R5") (pin "2") (pinfunction "2_2") (pintype "passive"))
    )
    (net (code "48") (name "Net-(U1-SPLIT)") (class "Default")
      (node (ref "C2") (pin "2") (pinfunction "2_2") (pintype "passive"))
      (node (ref "R1") (pin "2") (pinfunction "2_2") (pintype "passive"))
      (node (ref "R2") (pin "1") (pinfunction "1_1") (pintype "passive"))
      (node (ref "U1") (pin "5") (pinfunction "SPLIT_5") (pintype "passive"))
    )
    (net (code "49") (name "Net-(U2-OUT1)") (class "Default")
      (node (ref "TB1") (pin "2") (pinfunction "2_2") (pintype "passive"))
      (node (ref "U2") (pin "6") (pinfunction "OUT1_6") (pintype "output"))
    )
    (net (code "50") (name "Net-(U2-OUT2)") (class "Default")
      (node (ref "TB1") (pin "1") (pinfunction "1_1") (pintype "passive"))
      (node (ref "U2") (pin "8") (pinfunction "OUT2_8") (pintype "output"))
    )
    (net (code "51") (name "Net-(U2-RS)") (class "Default")
      (node (ref "R6") (pin "2") (pinfunction "2_2") (pintype "passive"))
      (node (ref "U2") (pin "7") (pinfunction "RS_7") (pintype "passive"))
    )
    (net (code "52") (name "Net-(U3-OUT1)") (class "Default")
      (node (ref "TB2") (pin "2") (pinfunction "2_2") (pintype "passive"))
      (node (ref "U3") (pin "6") (pinfunction "OUT1_6") (pintype "output"))
    )
    (net (code "53") (name "Net-(U3-OUT2)") (class "Default")
      (node (ref "TB2") (pin "1") (pinfunction "1_1") (pintype "passive"))
      (node (ref "U3") (pin "8") (pinfunction "OUT2_8") (pintype "output"))
    )
    (net (code "54") (name "Net-(U3-RS)") (class "Default")
      (node (ref "R7") (pin "2") (pinfunction "2_2") (pintype "passive"))
      (node (ref "U3") (pin "7") (pinfunction "RS_7") (pintype "passive"))
    )
    (net (code "55") (name "Net-(U4-OUT1)") (class "Default")
      (node (ref "TB3") (pin "2") (pinfunction "2_2") (pintype "passive"))
      (node (ref "U4") (pin "6") (pinfunction "OUT1_6") (pintype "output"))
    )
    (net (code "56") (name "Net-(U4-OUT2)") (class "Default")
      (node (ref "TB3") (pin "1") (pinfunction "1_1") (pintype "passive"))
      (node (ref "U4") (pin "8") (pinfunction "OUT2_8") (pintype "output"))
    )
    (net (code "57") (name "Net-(U4-RS)") (class "Default")
      (node (ref "R8") (pin "2") (pinfunction "2_2") (pintype "passive"))
      (node (ref "U4") (pin "7") (pinfunction "RS_7") (pintype "passive"))
    )
    (net (code "58") (name "Net-(U6-REF)") (class "Default")
      (node (ref "R10") (pin "1") (pinfunction "1_1") (pintype "passive"))
      (node (ref "R9") (pin "2") (pinfunction "2_2") (pintype "passive"))
      (node (ref "U6") (pin "1") (pinfunction "REF_1") (pintype "passive"))
    )
    (net (code "59") (name "Net-(U7-OUT1)") (class "Default")
      (node (ref "TB4") (pin "2") (pinfunction "2_2") (pintype "passive"))
      (node (ref "U7") (pin "6") (pinfunction "OUT1_6") (pintype "output"))
    )
    (net (code "60") (name "Net-(U7-OUT2)") (class "Default")
      (node (ref "TB4") (pin "1") (pinfunction "1_1") (pintype "passive"))
      (node (ref "U7") (pin "8") (pinfunction "OUT2_8") (pintype "output"))
    )
    (net (code "61") (name "Net-(U7-RS)") (class "Default")
      (node (ref "R11") (pin "2") (pinfunction "2_2") (pintype "passive"))
      (node (ref "U7") (pin "7") (pinfunction "RS_7") (pintype "passive"))
    )
    (net (code "62") (name "Net-(Z1-Anode)") (class "Default")
      (node (ref "Q1") (pin "G") (pinfunction "G_G") (pintype "passive"))
      (node (ref "R13") (pin "2") (pinfunction "2_2") (pintype "passive"))
      (node (ref "Z1") (pin "A") (pinfunction "Anode_A") (pintype "passive"))
    )
  )
)
